# iNDUCTIVE_LOOP.net
KiCad netlist of a schematic drawn in EAGLE
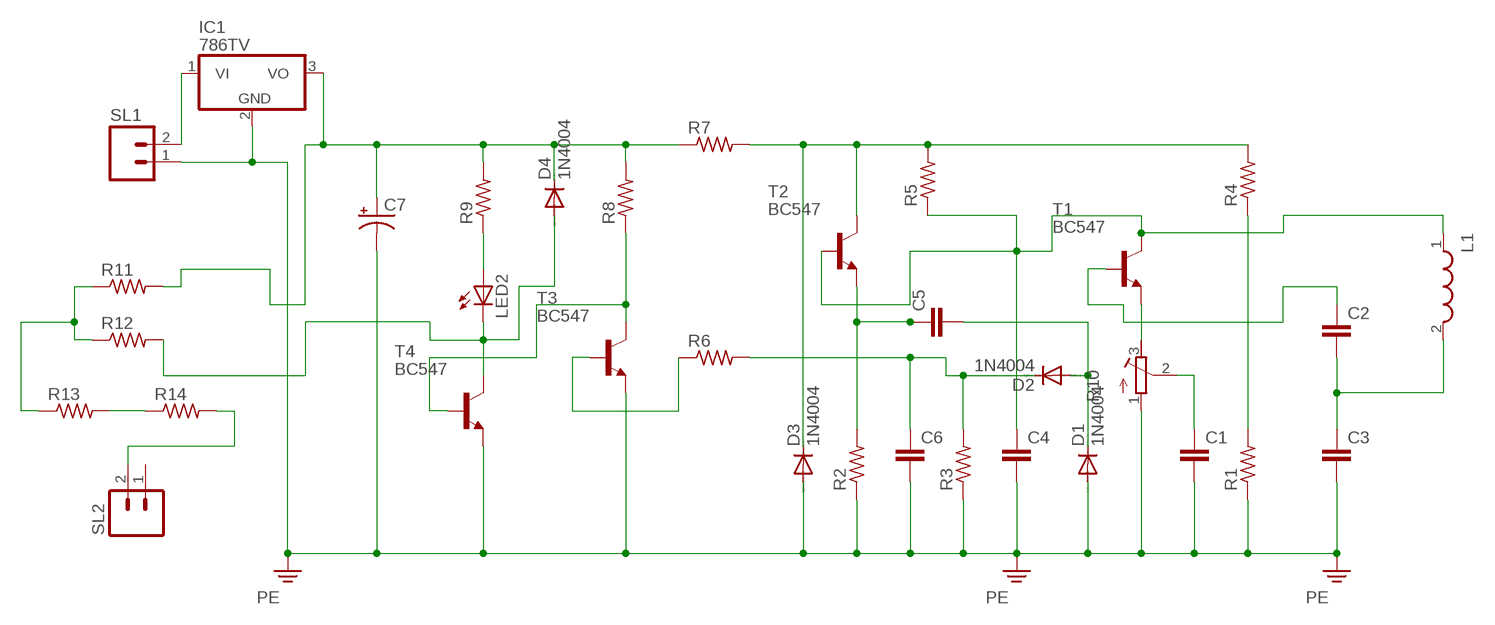
[diagram p0: schematic, sheet 1]

(export (version "E")
  (design (tool "Eeschema 10.0.6"))
  (components
    (comp (ref "C1")
      (value "C5/2.5")
      (footprint "eagle-import:C5B2.5")
      (libsource (lib "eagle-import") (part "C5/2.5"))
    )
    (comp (ref "C2")
      (value "C5/2.5")
      (footprint "eagle-import:C5B2.5")
      (libsource (lib "eagle-import") (part "C5/2.5"))
    )
    (comp (ref "C3")
      (value "C5/2.5")
      (footprint "eagle-import:C5B2.5")
      (libsource (lib "eagle-import") (part "C5/2.5"))
    )
    (comp (ref "C4")
      (value "C5/2.5")
      (footprint "eagle-import:C5B2.5")
      (libsource (lib "eagle-import") (part "C5/2.5"))
    )
    (comp (ref "C5")
      (value "C5/2.5")
      (footprint "eagle-import:C5B2.5")
      (libsource (lib "eagle-import") (part "C5/2.5"))
    )
    (comp (ref "C6")
      (value "C5/2.5")
      (footprint "eagle-import:C5B2.5")
      (libsource (lib "eagle-import") (part "C5/2.5"))
    )
    (comp (ref "C7")
      (value "CPOL-USE2.5-6")
      (footprint "eagle-import:E2,5-6")
      (libsource (lib "eagle-import") (part "CPOL-USE2.5-6"))
    )
    (comp (ref "D1")
      (value "1N4004")
      (footprint "eagle-import:DO41-10")
      (libsource (lib "eagle-import") (part "1N4004"))
    )
    (comp (ref "D2")
      (value "1N4004")
      (footprint "eagle-import:DO41-10")
      (libsource (lib "eagle-import") (part "1N4004"))
    )
    (comp (ref "D3")
      (value "1N4004")
      (footprint "eagle-import:DO41-10")
      (libsource (lib "eagle-import") (part "1N4004"))
    )
    (comp (ref "D4")
      (value "1N4004")
      (footprint "eagle-import:DO41-10")
      (libsource (lib "eagle-import") (part "1N4004"))
    )
    (comp (ref "IC1")
      (value "786TV")
      (footprint "eagle-import:TO220V")
      (libsource (lib "eagle-import") (part "78TV6"))
    )
    (comp (ref "L1")
      (value "WE-WPCC_1W_3737")
      (footprint "eagle-import:WE-WPCC_3737")
      (libsource (lib "eagle-import") (part "WE-WPCC_1W_3737"))
    )
    (comp (ref "LED2")
      (value "LEDLD260")
      (footprint "eagle-import:LD260")
      (libsource (lib "eagle-import") (part "LEDLD260"))
    )
    (comp (ref "R1")
      (value "R-US_0204/7")
      (footprint "eagle-import:0204_7")
      (libsource (lib "eagle-import") (part "R-US_0204/7"))
    )
    (comp (ref "R2")
      (value "R-US_0204/7")
      (footprint "eagle-import:0204_7")
      (libsource (lib "eagle-import") (part "R-US_0204/7"))
    )
    (comp (ref "R3")
      (value "R-US_0204/7")
      (footprint "eagle-import:0204_7")
      (libsource (lib "eagle-import") (part "R-US_0204/7"))
    )
    (comp (ref "R4")
      (value "R-US_0204/7")
      (footprint "eagle-import:0204_7")
      (libsource (lib "eagle-import") (part "R-US_0204/7"))
    )
    (comp (ref "R5")
      (value "R-US_0204/7")
      (footprint "eagle-import:0204_7")
      (libsource (lib "eagle-import") (part "R-US_0204/7"))
    )
    (comp (ref "R6")
      (value "R-US_0204/7")
      (footprint "eagle-import:0204_7")
      (libsource (lib "eagle-import") (part "R-US_0204/7"))
    )
    (comp (ref "R7")
      (value "R-US_0204/7")
      (footprint "eagle-import:0204_7")
      (libsource (lib "eagle-import") (part "R-US_0204/7"))
    )
    (comp (ref "R8")
      (value "R-US_0204/7")
      (footprint "eagle-import:0204_7")
      (libsource (lib "eagle-import") (part "R-US_0204/7"))
    )
    (comp (ref "R9")
      (value "R-US_0204/7")
      (footprint "eagle-import:0204_7")
      (libsource (lib "eagle-import") (part "R-US_0204/7"))
    )
    (comp (ref "R10")
      (value "R-TRIMM64P")
      (footprint "eagle-import:RTRIM64P")
      (libsource (lib "eagle-import") (part "R-TRIMM64P"))
    )
    (comp (ref "R11")
      (value "R-US_0204/7")
      (footprint "eagle-import:0204_7")
      (libsource (lib "eagle-import") (part "R-US_0204/7"))
    )
    (comp (ref "R12")
      (value "R-US_0204/7")
      (footprint "eagle-import:0204_7")
      (libsource (lib "eagle-import") (part "R-US_0204/7"))
    )
    (comp (ref "R13")
      (value "R-US_0204/7")
      (footprint "eagle-import:0204_7")
      (libsource (lib "eagle-import") (part "R-US_0204/7"))
    )
    (comp (ref "R14")
      (value "R-US_0204/7")
      (footprint "eagle-import:0204_7")
      (libsource (lib "eagle-import") (part "R-US_0204/7"))
    )
    (comp (ref "SL1")
      (value "MA02")
      (footprint "eagle-import:02PA")
      (libsource (lib "eagle-import") (part "MA02"))
    )
    (comp (ref "SL2")
      (value "MA02")
      (footprint "eagle-import:02PA")
      (libsource (lib "eagle-import") (part "MA02"))
    )
    (comp (ref "T1")
      (value "BC547")
      (footprint "eagle-import:TO92")
      (libsource (lib "eagle-import") (part "BC547"))
    )
    (comp (ref "T2")
      (value "BC547")
      (footprint "eagle-import:TO92")
      (libsource (lib "eagle-import") (part "BC547"))
    )
    (comp (ref "T3")
      (value "BC547")
      (footprint "eagle-import:TO92")
      (libsource (lib "eagle-import") (part "BC547"))
    )
    (comp (ref "T4")
      (value "BC547")
      (footprint "eagle-import:TO92")
      (libsource (lib "eagle-import") (part "BC547"))
    )
  )
  (nets
    (net (code "1") (name "Net-(C2-Pad2)") (class "Default")
      (node (ref "C2") (pin "2") (pinfunction "2_2") (pintype "passive"))
      (node (ref "C3") (pin "1") (pinfunction "1_1") (pintype "passive"))
      (node (ref "L1") (pin "2") (pinfunction "2_2") (pintype "passive"))
    )
    (net (code "2") (name "Net-(C5-Pad2)") (class "Default")
      (node (ref "C5") (pin "2") (pinfunction "2_2") (pintype "passive"))
      (node (ref "D1") (pin "C") (pinfunction "C_C") (pintype "passive"))
      (node (ref "D2") (pin "A") (pinfunction "A_A") (pintype "passive"))
    )
    (net (code "3") (name "Net-(C6-Pad1)") (class "Default")
      (node (ref "C6") (pin "1") (pinfunction "1_1") (pintype "passive"))
      (node (ref "D2") (pin "C") (pinfunction "C_C") (pintype "passive"))
      (node (ref "R3") (pin "2") (pinfunction "2_2") (pintype "passive"))
      (node (ref "R6") (pin "2") (pinfunction "2_2") (pintype "passive"))
    )
    (net (code "4") (name "Net-(IC1-VI)") (class "Default")
      (node (ref "IC1") (pin "1") (pinfunction "VI_1") (pintype "input"))
      (node (ref "SL1") (pin "2") (pinfunction "2_2") (pintype "passive"))
    )
    (net (code "5") (name "Net-(IC1-VO)") (class "Default")
      (node (ref "C7") (pin "+") (pinfunction "+_+") (pintype "passive"))
      (node (ref "D4") (pin "C") (pinfunction "C_C") (pintype "passive"))
      (node (ref "IC1") (pin "3") (pinfunction "VO_3") (pintype "passive"))
      (node (ref "R11") (pin "2") (pinfunction "2_2") (pintype "passive"))
      (node (ref "R7") (pin "1") (pinfunction "1_1") (pintype "passive"))
      (node (ref "R8") (pin "2") (pinfunction "2_2") (pintype "passive"))
      (node (ref "R9") (pin "2") (pinfunction "2_2") (pintype "passive"))
    )
    (net (code "6") (name "Net-(LED2-C)") (class "Default")
      (node (ref "D4") (pin "A") (pinfunction "A_A") (pintype "passive"))
      (node (ref "LED2") (pin "K") (pinfunction "C_K") (pintype "passive"))
      (node (ref "R12") (pin "2") (pinfunction "2_2") (pintype "passive"))
      (node (ref "T4") (pin "3") (pinfunction "C_3") (pintype "passive"))
    )
    (net (code "7") (name "Net-(LED2-PadA)") (class "Default")
      (node (ref "LED2") (pin "A") (pinfunction "A_A") (pintype "passive"))
      (node (ref "R9") (pin "1") (pinfunction "1_1") (pintype "passive"))
    )
    (net (code "8") (name "Net-(R1-Pad2)") (class "Default")
      (node (ref "R1") (pin "2") (pinfunction "2_2") (pintype "passive"))
      (node (ref "R4") (pin "1") (pinfunction "1_1") (pintype "passive"))
    )
    (net (code "9") (name "Net-(R10-E)") (class "Default")
      (node (ref "R10") (pin "3") (pinfunction "E_3") (pintype "passive"))
      (node (ref "T1") (pin "1") (pinfunction "E_1") (pintype "passive"))
    )
    (net (code "10") (name "Net-(R10-S)") (class "Default")
      (node (ref "C1") (pin "1") (pinfunction "1_1") (pintype "passive"))
      (node (ref "R10") (pin "2") (pinfunction "S_2") (pintype "passive"))
    )
    (net (code "11") (name "Net-(R11-Pad1)") (class "Default")
      (node (ref "R11") (pin "1") (pinfunction "1_1") (pintype "passive"))
      (node (ref "R12") (pin "1") (pinfunction "1_1") (pintype "passive"))
      (node (ref "R13") (pin "1") (pinfunction "1_1") (pintype "passive"))
    )
    (net (code "12") (name "Net-(R13-Pad2)") (class "Default")
      (node (ref "R13") (pin "2") (pinfunction "2_2") (pintype "passive"))
      (node (ref "R14") (pin "1") (pinfunction "1_1") (pintype "passive"))
    )
    (net (code "13") (name "Net-(R14-Pad2)") (class "Default")
      (node (ref "R14") (pin "2") (pinfunction "2_2") (pintype "passive"))
      (node (ref "SL2") (pin "2") (pinfunction "2_2") (pintype "passive"))
    )
    (net (code "14") (name "Net-(T1-B)") (class "Default")
      (node (ref "C2") (pin "1") (pinfunction "1_1") (pintype "passive"))
      (node (ref "T1") (pin "2") (pinfunction "B_2") (pintype "passive"))
    )
    (net (code "15") (name "Net-(T1-C)") (class "Default")
      (node (ref "C4") (pin "1") (pinfunction "1_1") (pintype "passive"))
      (node (ref "L1") (pin "1") (pinfunction "1_1") (pintype "passive"))
      (node (ref "R5") (pin "1") (pinfunction "1_1") (pintype "passive"))
      (node (ref "T1") (pin "3") (pinfunction "C_3") (pintype "passive"))
      (node (ref "T2") (pin "2") (pinfunction "B_2") (pintype "passive"))
    )
    (net (code "16") (name "Net-(T2-C)") (class "Default")
      (node (ref "D3") (pin "C") (pinfunction "C_C") (pintype "passive"))
      (node (ref "R4") (pin "2") (pinfunction "2_2") (pintype "passive"))
      (node (ref "R5") (pin "2") (pinfunction "2_2") (pintype "passive"))
      (node (ref "R7") (pin "2") (pinfunction "2_2") (pintype "passive"))
      (node (ref "T2") (pin "3") (pinfunction "C_3") (pintype "passive"))
    )
    (net (code "17") (name "Net-(T2-E)") (class "Default")
      (node (ref "C5") (pin "1") (pinfunction "1_1") (pintype "passive"))
      (node (ref "R2") (pin "2") (pinfunction "2_2") (pintype "passive"))
      (node (ref "T2") (pin "1") (pinfunction "E_1") (pintype "passive"))
    )
    (net (code "18") (name "Net-(T3-B)") (class "Default")
      (node (ref "R6") (pin "1") (pinfunction "1_1") (pintype "passive"))
      (node (ref "T3") (pin "2") (pinfunction "B_2") (pintype "passive"))
    )
    (net (code "19") (name "Net-(T3-C)") (class "Default")
      (node (ref "R8") (pin "1") (pinfunction "1_1") (pintype "passive"))
      (node (ref "T3") (pin "3") (pinfunction "C_3") (pintype "passive"))
      (node (ref "T4") (pin "2") (pinfunction "B_2") (pintype "passive"))
    )
    (net (code "20") (name "PE") (class "Default")
      (node (ref "C1") (pin "2") (pinfunction "2_2") (pintype "passive"))
      (node (ref "C3") (pin "2") (pinfunction "2_2") (pintype "passive"))
      (node (ref "C4") (pin "2") (pinfunction "2_2") (pintype "passive"))
      (node (ref "C6") (pin "2") (pinfunction "2_2") (pintype "passive"))
      (node (ref "C7") (pin "-") (pinfunction "-_-") (pintype "passive"))
      (node (ref "D1") (pin "A") (pinfunction "A_A") (pintype "passive"))
      (node (ref "D3") (pin "A") (pinfunction "A_A") (pintype "passive"))
      (node (ref "IC1") (pin "2") (pinfunction "GND_2") (pintype "passive"))
      (node (ref "R1") (pin "1") (pinfunction "1_1") (pintype "passive"))
      (node (ref "R10") (pin "1") (pinfunction "A_1") (pintype "passive"))
      (node (ref "R2") (pin "1") (pinfunction "1_1") (pintype "passive"))
      (node (ref "R3") (pin "1") (pinfunction "1_1") (pintype "passive"))
      (node (ref "SL1") (pin "1") (pinfunction "1_1") (pintype "passive"))
      (node (ref "T3") (pin "1") (pinfunction "E_1") (pintype "passive"))
      (node (ref "T4") (pin "1") (pinfunction "E_1") (pintype "passive"))
    )
    (net (code "21") (name "unconnected-(SL2-Pad1)") (class "Default")
      (node (ref "SL2") (pin "1") (pinfunction "1_1") (pintype "passive"))
    )
  )
)
